# Block.net
KiCad netlist of a schematic drawn in Altium Designer
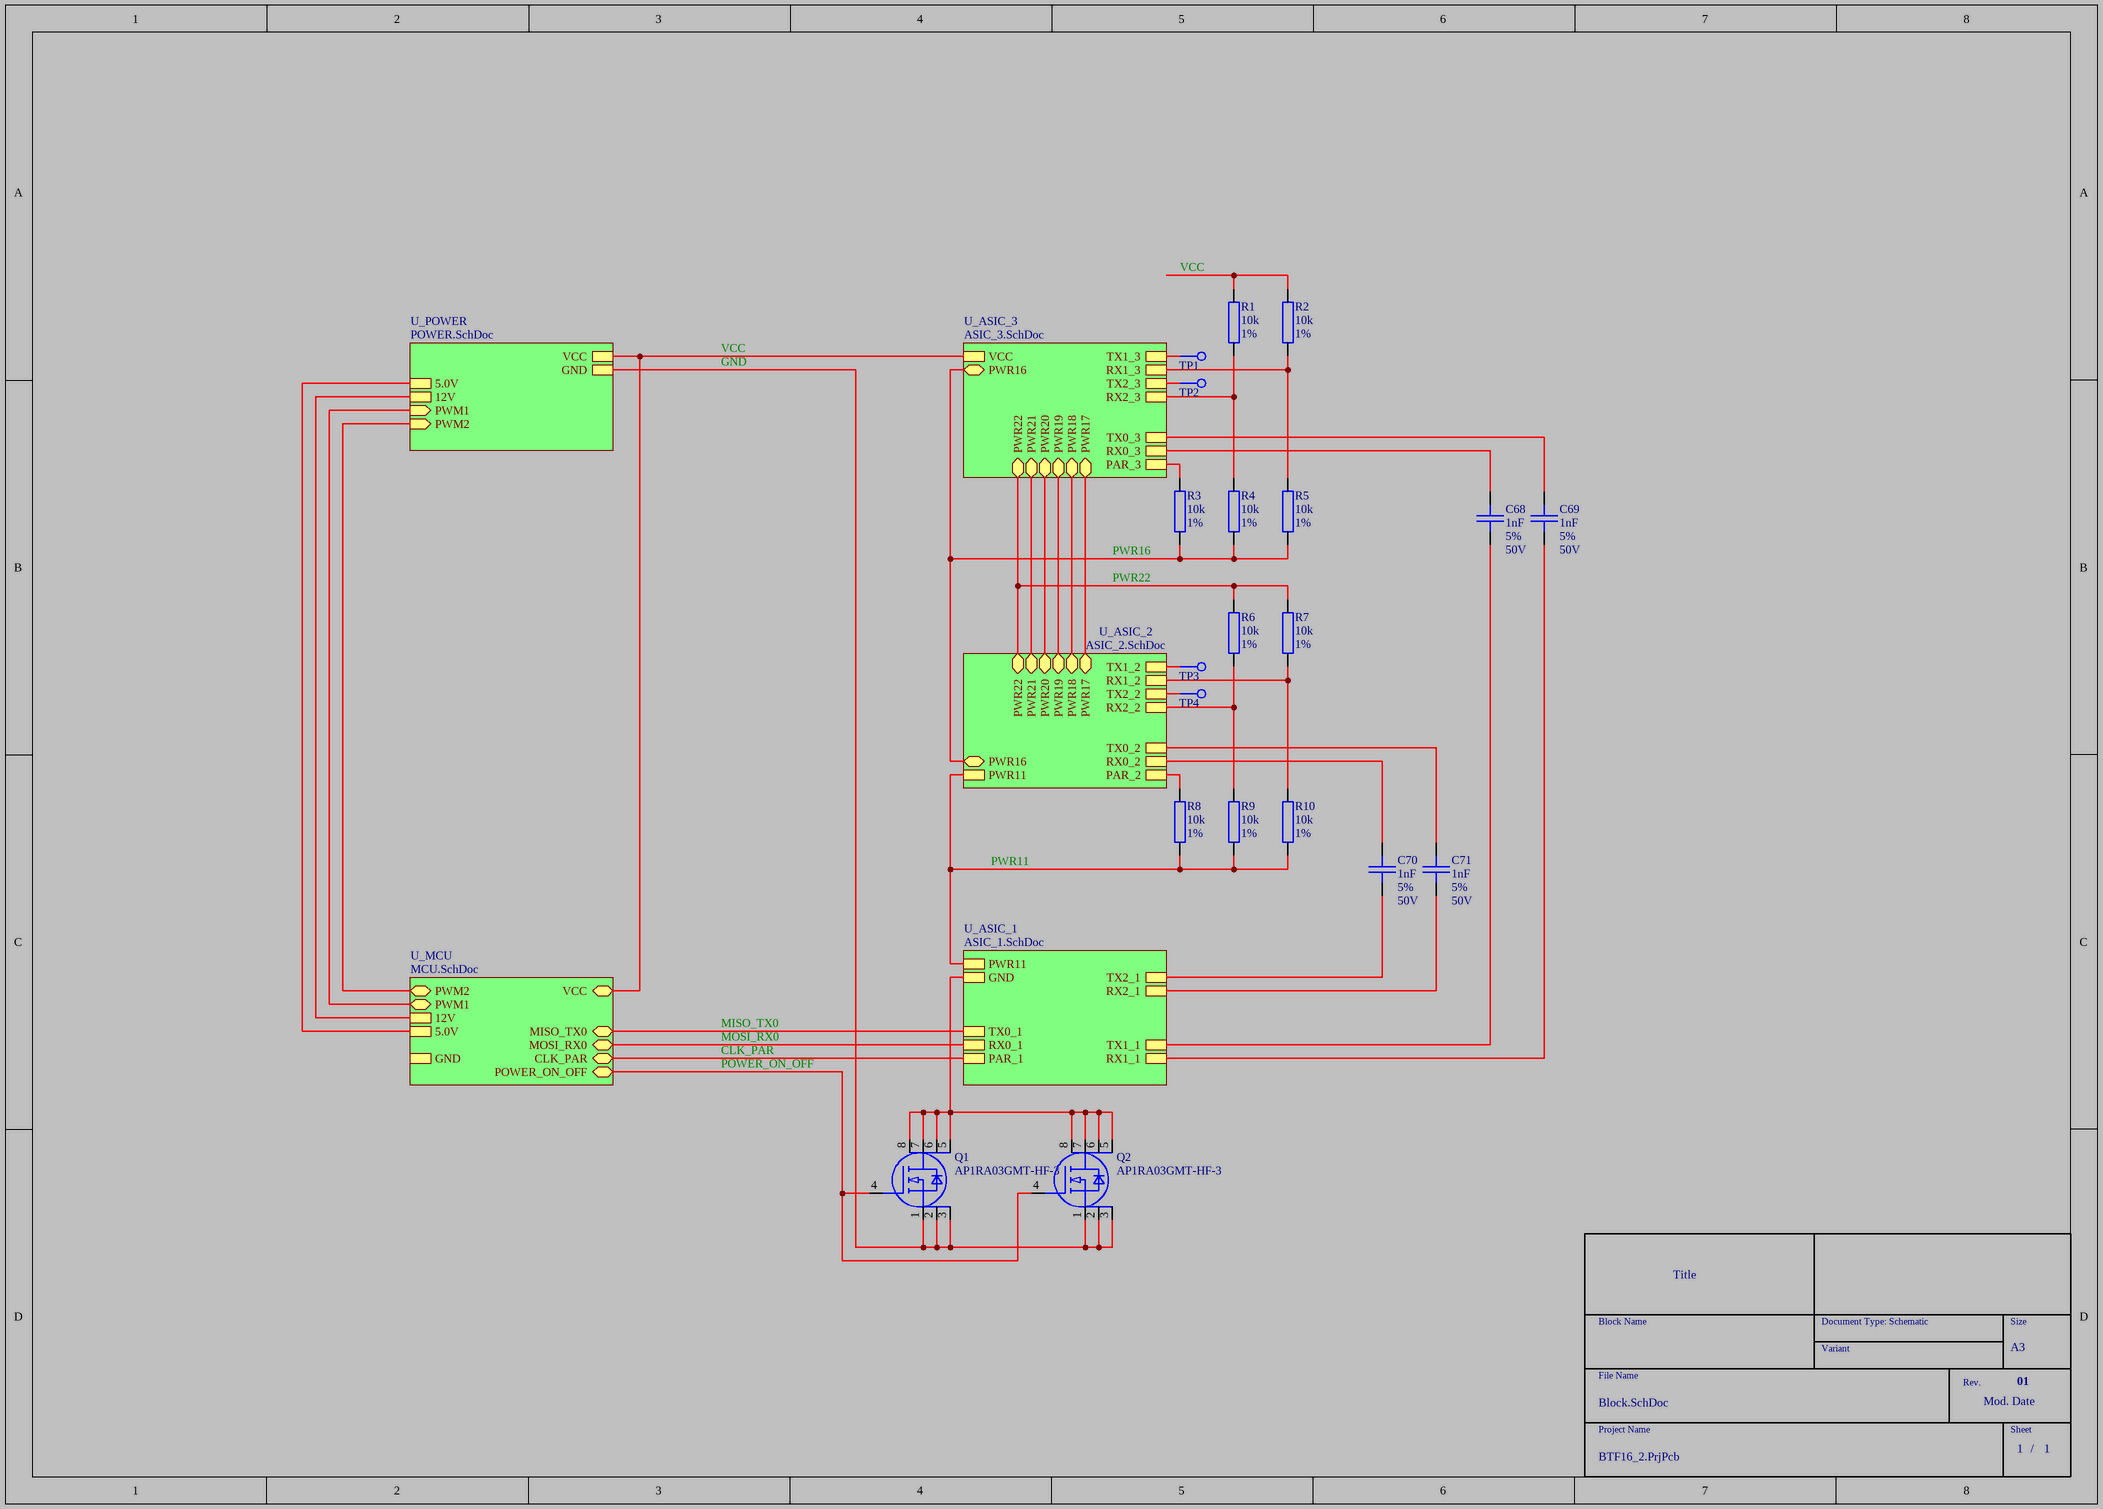
[diagram p0: Block.SchDoc]

(export (version "E")
  (design (tool "Eeschema 10.0.6"))
  (components
    (comp (ref "C68")
      (value "C")
      (footprint "SMD_0603_CAPC1608X95N")
      (fields
        (field (name "DB_PART_NUMBER") "CAP000020649")
        (field (name "DB_VALUE") "1nF")
        (field (name "DB_TOLERANCE") "5%")
        (field (name "DB_VOLTAGE") "50V")
        (field (name "DB_MANUFACTURER_PART") "KEMET    C0603F102J5RAC")
      )
      (libsource (lib "Database_Libs1") (part "C"))
    )
    (comp (ref "C69")
      (value "C")
      (footprint "SMD_0603_CAPC1608X95N")
      (fields
        (field (name "DB_PART_NUMBER") "CAP000020649")
        (field (name "DB_VALUE") "1nF")
        (field (name "DB_TOLERANCE") "5%")
        (field (name "DB_VOLTAGE") "50V")
        (field (name "DB_MANUFACTURER_PART") "KEMET    C0603F102J5RAC")
      )
      (libsource (lib "Database_Libs1") (part "C"))
    )
    (comp (ref "C70")
      (value "C")
      (footprint "SMD_0603_CAPC1608X95N")
      (fields
        (field (name "DB_PART_NUMBER") "CAP000020649")
        (field (name "DB_VALUE") "1nF")
        (field (name "DB_TOLERANCE") "5%")
        (field (name "DB_VOLTAGE") "50V")
        (field (name "DB_MANUFACTURER_PART") "KEMET    C0603F102J5RAC")
      )
      (libsource (lib "Database_Libs1") (part "C"))
    )
    (comp (ref "C71")
      (value "C")
      (footprint "SMD_0603_CAPC1608X95N")
      (fields
        (field (name "DB_PART_NUMBER") "CAP000020649")
        (field (name "DB_VALUE") "1nF")
        (field (name "DB_TOLERANCE") "5%")
        (field (name "DB_VOLTAGE") "50V")
        (field (name "DB_MANUFACTURER_PART") "KEMET    C0603F102J5RAC")
      )
      (libsource (lib "Database_Libs1") (part "C"))
    )
    (comp (ref "Q1")
      (value "MOS_N_D1_S1S2S3G4D5D6D7D8")
      (footprint "SMD_SOIC127P600X110-9AN")
      (fields
        (field (name "DB_PART_NUMBER") "TRA000001604")
        (field (name "DB_VALUE") "AP1RA03GMT-HF-3")
        (field (name "DB_MANUFACTURER_PART") "ADVANCED POWER ELECTRONICS CORP      AP1RA03GMT-HF-3")
        (field (name "DB_APPROVED_BY") "VSN")
      )
      (libsource (lib "Database_Libs1") (part "MOS_N_D1_S1S2S3G4D5D6D7D8"))
    )
    (comp (ref "Q2")
      (value "MOS_N_D1_S1S2S3G4D5D6D7D8")
      (footprint "SMD_SOIC127P600X110-9AN")
      (fields
        (field (name "DB_PART_NUMBER") "TRA000001604")
        (field (name "DB_VALUE") "AP1RA03GMT-HF-3")
        (field (name "DB_MANUFACTURER_PART") "ADVANCED POWER ELECTRONICS CORP      AP1RA03GMT-HF-3")
        (field (name "DB_APPROVED_BY") "VSN")
      )
      (libsource (lib "Database_Libs1") (part "MOS_N_D1_S1S2S3G4D5D6D7D8"))
    )
    (comp (ref "R1")
      (value "R")
      (footprint "SMD_0603_RESC1608X55N")
      (fields
        (field (name "DB_PART_NUMBER") "RES000008891")
        (field (name "DB_VALUE") "10k")
        (field (name "DB_TOLERANCE") "1%")
        (field (name "DB_MANUFACTURER_PART") "VISHAY    CRCW060310K0FKEA")
        (field (name "DB_APPROVED_BY") "VSN")
      )
      (libsource (lib "Database_Libs1") (part "R"))
    )
    (comp (ref "R2")
      (value "R")
      (footprint "SMD_0603_RESC1608X55N")
      (fields
        (field (name "DB_PART_NUMBER") "RES000008891")
        (field (name "DB_VALUE") "10k")
        (field (name "DB_TOLERANCE") "1%")
        (field (name "DB_MANUFACTURER_PART") "VISHAY    CRCW060310K0FKEA")
        (field (name "DB_APPROVED_BY") "VSN")
      )
      (libsource (lib "Database_Libs1") (part "R"))
    )
    (comp (ref "R3")
      (value "R")
      (footprint "SMD_0603_RESC1608X55N")
      (fields
        (field (name "DB_PART_NUMBER") "RES000008891")
        (field (name "DB_VALUE") "10k")
        (field (name "DB_TOLERANCE") "1%")
        (field (name "DB_MANUFACTURER_PART") "VISHAY    CRCW060310K0FKEA")
        (field (name "DB_APPROVED_BY") "VSN")
      )
      (libsource (lib "Database_Libs1") (part "R"))
    )
    (comp (ref "R4")
      (value "R")
      (footprint "SMD_0603_RESC1608X55N")
      (fields
        (field (name "DB_PART_NUMBER") "RES000008891")
        (field (name "DB_VALUE") "10k")
        (field (name "DB_TOLERANCE") "1%")
        (field (name "DB_MANUFACTURER_PART") "VISHAY    CRCW060310K0FKEA")
        (field (name "DB_APPROVED_BY") "VSN")
      )
      (libsource (lib "Database_Libs1") (part "R"))
    )
    (comp (ref "R5")
      (value "R")
      (footprint "SMD_0603_RESC1608X55N")
      (fields
        (field (name "DB_PART_NUMBER") "RES000008891")
        (field (name "DB_VALUE") "10k")
        (field (name "DB_TOLERANCE") "1%")
        (field (name "DB_MANUFACTURER_PART") "VISHAY    CRCW060310K0FKEA")
        (field (name "DB_APPROVED_BY") "VSN")
      )
      (libsource (lib "Database_Libs1") (part "R"))
    )
    (comp (ref "R6")
      (value "R")
      (footprint "SMD_0603_RESC1608X55N")
      (fields
        (field (name "DB_PART_NUMBER") "RES000008891")
        (field (name "DB_VALUE") "10k")
        (field (name "DB_TOLERANCE") "1%")
        (field (name "DB_MANUFACTURER_PART") "VISHAY    CRCW060310K0FKEA")
        (field (name "DB_APPROVED_BY") "VSN")
      )
      (libsource (lib "Database_Libs1") (part "R"))
    )
    (comp (ref "R7")
      (value "R")
      (footprint "SMD_0603_RESC1608X55N")
      (fields
        (field (name "DB_PART_NUMBER") "RES000008891")
        (field (name "DB_VALUE") "10k")
        (field (name "DB_TOLERANCE") "1%")
        (field (name "DB_MANUFACTURER_PART") "VISHAY    CRCW060310K0FKEA")
        (field (name "DB_APPROVED_BY") "VSN")
      )
      (libsource (lib "Database_Libs1") (part "R"))
    )
    (comp (ref "R8")
      (value "R")
      (footprint "SMD_0603_RESC1608X55N")
      (fields
        (field (name "DB_PART_NUMBER") "RES000008891")
        (field (name "DB_VALUE") "10k")
        (field (name "DB_TOLERANCE") "1%")
        (field (name "DB_MANUFACTURER_PART") "VISHAY    CRCW060310K0FKEA")
        (field (name "DB_APPROVED_BY") "VSN")
      )
      (libsource (lib "Database_Libs1") (part "R"))
    )
    (comp (ref "R9")
      (value "R")
      (footprint "SMD_0603_RESC1608X55N")
      (fields
        (field (name "DB_PART_NUMBER") "RES000008891")
        (field (name "DB_VALUE") "10k")
        (field (name "DB_TOLERANCE") "1%")
        (field (name "DB_MANUFACTURER_PART") "VISHAY    CRCW060310K0FKEA")
        (field (name "DB_APPROVED_BY") "VSN")
      )
      (libsource (lib "Database_Libs1") (part "R"))
    )
    (comp (ref "R10")
      (value "R")
      (footprint "SMD_0603_RESC1608X55N")
      (fields
        (field (name "DB_PART_NUMBER") "RES000008891")
        (field (name "DB_VALUE") "10k")
        (field (name "DB_TOLERANCE") "1%")
        (field (name "DB_MANUFACTURER_PART") "VISHAY    CRCW060310K0FKEA")
        (field (name "DB_APPROVED_BY") "VSN")
      )
      (libsource (lib "Database_Libs1") (part "R"))
    )
    (comp (ref "TP1")
      (value "TEST_POINT_1")
      (footprint "SMD_TP_100-254")
      (fields (field (name "DB_PART_NUMBER") "TPO000000001"))
      (libsource (lib "Database_Libs1") (part "TEST_POINT_1"))
    )
    (comp (ref "TP2")
      (value "TEST_POINT_1")
      (footprint "SMD_TP_100-254")
      (fields (field (name "DB_PART_NUMBER") "TPO000000001"))
      (libsource (lib "Database_Libs1") (part "TEST_POINT_1"))
    )
    (comp (ref "TP3")
      (value "TEST_POINT_1")
      (footprint "SMD_TP_100-254")
      (fields (field (name "DB_PART_NUMBER") "TPO000000001"))
      (libsource (lib "Database_Libs1") (part "TEST_POINT_1"))
    )
    (comp (ref "TP4")
      (value "TEST_POINT_1")
      (footprint "SMD_TP_100-254")
      (fields (field (name "DB_PART_NUMBER") "TPO000000001"))
      (libsource (lib "Database_Libs1") (part "TEST_POINT_1"))
    )
  )
  (nets
    (net (code "4") (name "/GND") (class "Default")
      (node (ref "Q1") (pin "1") (pinfunction "S_1") (pintype "passive"))
      (node (ref "Q1") (pin "2") (pinfunction "S_2") (pintype "passive"))
      (node (ref "Q1") (pin "3") (pinfunction "S_3") (pintype "passive"))
      (node (ref "Q2") (pin "1") (pinfunction "S_1") (pintype "passive"))
      (node (ref "Q2") (pin "2") (pinfunction "S_2") (pintype "passive"))
      (node (ref "Q2") (pin "3") (pinfunction "S_3") (pintype "passive"))
    )
    (net (code "5") (name "/GND_1") (class "Default")
      (node (ref "Q1") (pin "5") (pinfunction "D_5") (pintype "passive"))
      (node (ref "Q1") (pin "6") (pinfunction "D_6") (pintype "passive"))
      (node (ref "Q1") (pin "7") (pinfunction "D_7") (pintype "passive"))
      (node (ref "Q1") (pin "8") (pinfunction "D_8") (pintype "passive"))
      (node (ref "Q2") (pin "5") (pinfunction "D_5") (pintype "passive"))
      (node (ref "Q2") (pin "6") (pinfunction "D_6") (pintype "passive"))
      (node (ref "Q2") (pin "7") (pinfunction "D_7") (pintype "passive"))
      (node (ref "Q2") (pin "8") (pinfunction "D_8") (pintype "passive"))
    )
    (net (code "9") (name "/PAR_2") (class "Default")
      (node (ref "R8") (pin "1") (pinfunction "1_1") (pintype "passive"))
    )
    (net (code "10") (name "/PAR_3") (class "Default")
      (node (ref "R3") (pin "1") (pinfunction "1_1") (pintype "passive"))
    )
    (net (code "11") (name "/POWER_ON_OFF") (class "Default")
      (node (ref "Q1") (pin "4") (pinfunction "G_4") (pintype "passive"))
      (node (ref "Q2") (pin "4") (pinfunction "G_4") (pintype "passive"))
    )
    (net (code "14") (name "/PWR11") (class "Default")
      (node (ref "R10") (pin "2") (pinfunction "2_2") (pintype "passive"))
      (node (ref "R8") (pin "2") (pinfunction "2_2") (pintype "passive"))
      (node (ref "R9") (pin "2") (pinfunction "2_2") (pintype "passive"))
    )
    (net (code "15") (name "/PWR16") (class "Default")
      (node (ref "R3") (pin "2") (pinfunction "2_2") (pintype "passive"))
      (node (ref "R4") (pin "2") (pinfunction "2_2") (pintype "passive"))
      (node (ref "R5") (pin "2") (pinfunction "2_2") (pintype "passive"))
    )
    (net (code "21") (name "/PWR22") (class "Default")
      (node (ref "R6") (pin "2") (pinfunction "2_2") (pintype "passive"))
      (node (ref "R7") (pin "2") (pinfunction "2_2") (pintype "passive"))
    )
    (net (code "22") (name "/RX0_2") (class "Default")
      (node (ref "C70") (pin "1") (pinfunction "1_1") (pintype "passive"))
    )
    (net (code "23") (name "/RX0_3") (class "Default")
      (node (ref "C68") (pin "1") (pinfunction "1_1") (pintype "passive"))
    )
    (net (code "24") (name "/RX1_1") (class "Default")
      (node (ref "C69") (pin "2") (pinfunction "2_2") (pintype "passive"))
    )
    (net (code "25") (name "/RX1_2") (class "Default")
      (node (ref "R10") (pin "1") (pinfunction "1_1") (pintype "passive"))
      (node (ref "R7") (pin "1") (pinfunction "1_1") (pintype "passive"))
    )
    (net (code "26") (name "/RX1_3") (class "Default")
      (node (ref "R2") (pin "1") (pinfunction "1_1") (pintype "passive"))
      (node (ref "R5") (pin "1") (pinfunction "1_1") (pintype "passive"))
    )
    (net (code "27") (name "/RX2_1") (class "Default")
      (node (ref "C71") (pin "2") (pinfunction "2_2") (pintype "passive"))
    )
    (net (code "28") (name "/RX2_2") (class "Default")
      (node (ref "R6") (pin "1") (pinfunction "1_1") (pintype "passive"))
      (node (ref "R9") (pin "1") (pinfunction "1_1") (pintype "passive"))
    )
    (net (code "29") (name "/RX2_3") (class "Default")
      (node (ref "R1") (pin "1") (pinfunction "1_1") (pintype "passive"))
      (node (ref "R4") (pin "1") (pinfunction "1_1") (pintype "passive"))
    )
    (net (code "30") (name "/TX0_2") (class "Default")
      (node (ref "C71") (pin "1") (pinfunction "1_1") (pintype "passive"))
    )
    (net (code "31") (name "/TX0_3") (class "Default")
      (node (ref "C69") (pin "1") (pinfunction "1_1") (pintype "passive"))
    )
    (net (code "32") (name "/TX1_1") (class "Default")
      (node (ref "C68") (pin "2") (pinfunction "2_2") (pintype "passive"))
    )
    (net (code "33") (name "/TX1_2") (class "Default")
      (node (ref "TP3") (pin "1") (pinfunction "1_1") (pintype "passive"))
    )
    (net (code "34") (name "/TX1_3") (class "Default")
      (node (ref "TP1") (pin "1") (pinfunction "1_1") (pintype "passive"))
    )
    (net (code "35") (name "/TX2_1") (class "Default")
      (node (ref "C70") (pin "2") (pinfunction "2_2") (pintype "passive"))
    )
    (net (code "36") (name "/TX2_2") (class "Default")
      (node (ref "TP4") (pin "1") (pinfunction "1_1") (pintype "passive"))
    )
    (net (code "37") (name "/TX2_3") (class "Default")
      (node (ref "TP2") (pin "1") (pinfunction "1_1") (pintype "passive"))
    )
    (net (code "38") (name "/VCC") (class "Default")
      (node (ref "R1") (pin "2") (pinfunction "2_2") (pintype "passive"))
      (node (ref "R2") (pin "2") (pinfunction "2_2") (pintype "passive"))
    )
  )
)
